# Schematic.net
KiCad netlist of a schematic drawn in EAGLE
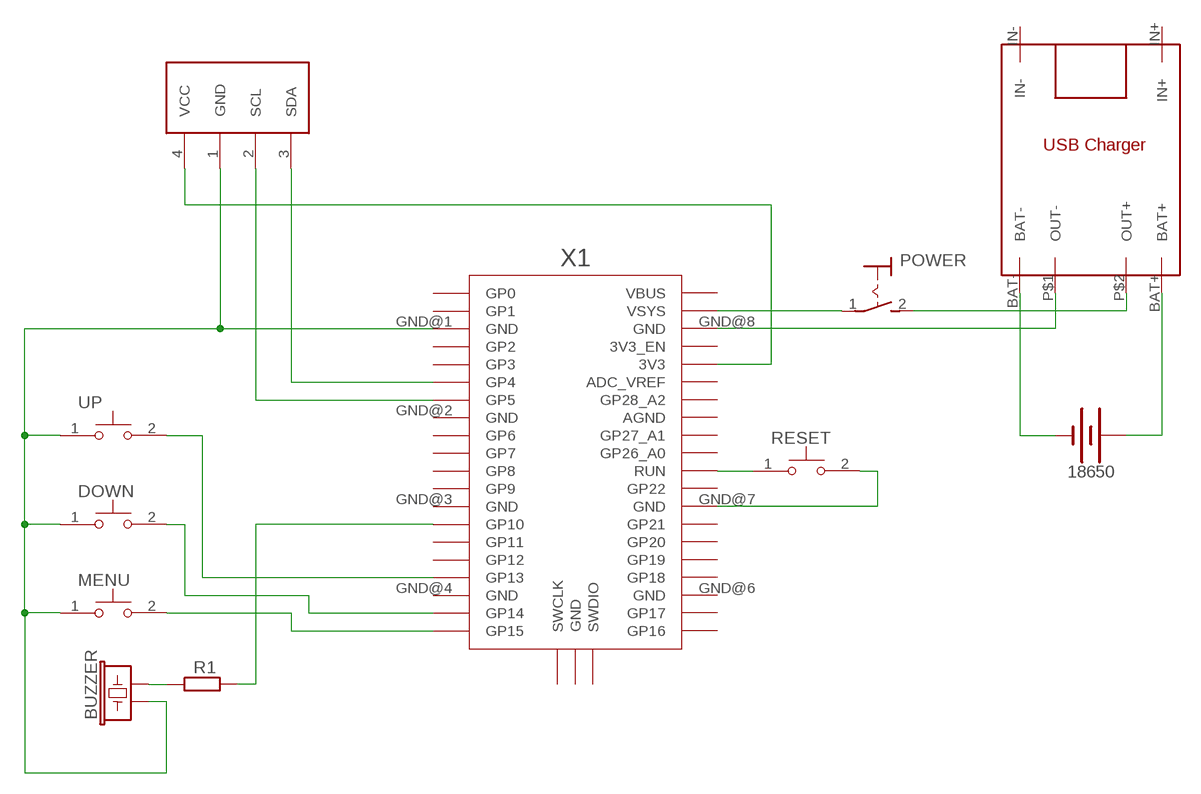
[diagram p0: schematic, sheet 1]

(export (version "E")
  (design (tool "Eeschema 10.0.6"))
  (components
    (comp (ref "18650")
      (value "BATTERY-18650")
      (footprint "eagle-import:BATTERY_18650-HOLDER")
      (libsource (lib "eagle-import") (part "BATTERY-18650"))
    )
    (comp (ref "BUZZER")
      (value "BUZZER-PTH_KIT")
      (footprint "eagle-import:BUZZER-12MM-KIT")
      (libsource (lib "eagle-import") (part "BUZZER-PTH_KIT"))
    )
    (comp (ref "DOWN")
      (value "BUTT-2")
      (footprint "eagle-import:SW_BUTT-2")
      (fields (field (name "MF") "Gravitech"))
      (libsource (lib "eagle-import") (part "BUTT-2"))
    )
    (comp (ref "MENU")
      (value "BUTT-2")
      (footprint "eagle-import:SW_BUTT-2")
      (fields (field (name "MF") "Gravitech"))
      (libsource (lib "eagle-import") (part "BUTT-2"))
    )
    (comp (ref "POWER")
      (value "MS243")
      (footprint "eagle-import:MS243")
      (libsource (lib "eagle-import") (part "MS243"))
    )
    (comp (ref "R1")
      (value "R-EU_0207/10")
      (footprint "eagle-import:0207_10")
      (libsource (lib "eagle-import") (part "R-EU_0207/10"))
    )
    (comp (ref "RESET")
      (value "BUTT-2")
      (footprint "eagle-import:SW_BUTT-2")
      (fields (field (name "MF") "Gravitech"))
      (libsource (lib "eagle-import") (part "BUTT-2"))
    )
    (comp (ref "U$1")
      (value "I2C_OLED")
      (footprint "eagle-import:I2C_OLED_PACKAGE")
      (libsource (lib "eagle-import") (part "I2C_OLED"))
    )
    (comp (ref "U$2")
      (value "TP4056")
      (footprint "eagle-import:TP4056")
      (libsource (lib "eagle-import") (part "TP4056"))
    )
    (comp (ref "UP")
      (value "BUTT-2")
      (footprint "eagle-import:SW_BUTT-2")
      (fields (field (name "MF") "Gravitech"))
      (libsource (lib "eagle-import") (part "BUTT-2"))
    )
    (comp (ref "X1")
      (value "RPI_PICO_IG-TH")
      (footprint "eagle-import:RPI_PICO_TH")
      (libsource (lib "eagle-import") (part "RPI_PICO_IG-TH"))
    )
  )
  (nets
    (net (code "1") (name "Net-(18650-+)") (class "Default")
      (node (ref "18650") (pin "PWR@1") (pinfunction "+_PWR@1") (pintype "power_in"))
      (node (ref "U$2") (pin "BAT+") (pinfunction "BAT+_BAT+") (pintype "bidirectional"))
    )
    (net (code "2") (name "Net-(18650--)") (class "Default")
      (node (ref "18650") (pin "GND@1") (pinfunction "-_GND@1") (pintype "power_in"))
      (node (ref "U$2") (pin "BAT-") (pinfunction "BAT-_BAT-") (pintype "bidirectional"))
    )
    (net (code "3") (name "Net-(BUZZER-1)") (class "Default")
      (node (ref "BUZZER") (pin "+") (pinfunction "1_+") (pintype "passive"))
      (node (ref "DOWN") (pin "1") (pinfunction "1_1") (pintype "passive"))
      (node (ref "MENU") (pin "1") (pinfunction "1_1") (pintype "passive"))
      (node (ref "U$1") (pin "1") (pinfunction "GND_1") (pintype "bidirectional"))
      (node (ref "UP") (pin "1") (pinfunction "1_1") (pintype "passive"))
      (node (ref "X1") (pin "GND@1") (pinfunction "GND_GND@1") (pintype "bidirectional"))
    )
    (net (code "4") (name "Net-(BUZZER-2)") (class "Default")
      (node (ref "BUZZER") (pin "-") (pinfunction "2_-") (pintype "passive"))
      (node (ref "R1") (pin "1") (pinfunction "1_1") (pintype "passive"))
    )
    (net (code "5") (name "Net-(DOWN-Pad2)") (class "Default")
      (node (ref "DOWN") (pin "2") (pinfunction "2_2") (pintype "passive"))
      (node (ref "X1") (pin "GP14") (pinfunction "GP14_GP14") (pintype "bidirectional"))
    )
    (net (code "6") (name "Net-(MENU-Pad2)") (class "Default")
      (node (ref "MENU") (pin "2") (pinfunction "2_2") (pintype "passive"))
      (node (ref "X1") (pin "GP15") (pinfunction "GP15_GP15") (pintype "bidirectional"))
    )
    (net (code "7") (name "Net-(POWER-P)") (class "Default")
      (node (ref "POWER") (pin "1") (pinfunction "P_1") (pintype "passive"))
      (node (ref "X1") (pin "VSYS") (pinfunction "VSYS_VSYS") (pintype "bidirectional"))
    )
    (net (code "8") (name "Net-(POWER-S)") (class "Default")
      (node (ref "POWER") (pin "2") (pinfunction "S_2") (pintype "passive"))
      (node (ref "U$2") (pin "P$2") (pinfunction "OUT+_P$2") (pintype "bidirectional"))
    )
    (net (code "9") (name "Net-(R1-Pad2)") (class "Default")
      (node (ref "R1") (pin "2") (pinfunction "2_2") (pintype "passive"))
      (node (ref "X1") (pin "GP10") (pinfunction "GP10_GP10") (pintype "bidirectional"))
    )
    (net (code "10") (name "Net-(RESET-Pad1)") (class "Default")
      (node (ref "RESET") (pin "1") (pinfunction "1_1") (pintype "passive"))
      (node (ref "X1") (pin "RUN") (pinfunction "RUN_RUN") (pintype "bidirectional"))
    )
    (net (code "11") (name "Net-(RESET-Pad2)") (class "Default")
      (node (ref "RESET") (pin "2") (pinfunction "2_2") (pintype "passive"))
      (node (ref "X1") (pin "GND@7") (pinfunction "GND_GND@7") (pintype "bidirectional"))
    )
    (net (code "12") (name "Net-(U$1-SCL)") (class "Default")
      (node (ref "U$1") (pin "2") (pinfunction "SCL_2") (pintype "bidirectional"))
      (node (ref "X1") (pin "GP5") (pinfunction "GP5_GP5") (pintype "bidirectional"))
    )
    (net (code "13") (name "Net-(U$1-SDA)") (class "Default")
      (node (ref "U$1") (pin "3") (pinfunction "SDA_3") (pintype "bidirectional"))
      (node (ref "X1") (pin "GP4") (pinfunction "GP4_GP4") (pintype "bidirectional"))
    )
    (net (code "14") (name "Net-(U$1-VCC)") (class "Default")
      (node (ref "U$1") (pin "4") (pinfunction "VCC_4") (pintype "bidirectional"))
      (node (ref "X1") (pin "3V3") (pinfunction "3V3_3V3") (pintype "bidirectional"))
    )
    (net (code "15") (name "Net-(U$2-OUT-)") (class "Default")
      (node (ref "U$2") (pin "P$1") (pinfunction "OUT-_P$1") (pintype "bidirectional"))
      (node (ref "X1") (pin "GND@8") (pinfunction "GND_GND@8") (pintype "bidirectional"))
    )
    (net (code "16") (name "Net-(UP-Pad2)") (class "Default")
      (node (ref "UP") (pin "2") (pinfunction "2_2") (pintype "passive"))
      (node (ref "X1") (pin "GP13") (pinfunction "GP13_GP13") (pintype "bidirectional"))
    )
    (net (code "17") (name "unconnected-(U$2-PadIN+)") (class "Default")
      (node (ref "U$2") (pin "IN+") (pinfunction "IN+_IN+") (pintype "bidirectional"))
    )
    (net (code "18") (name "unconnected-(U$2-PadIN-)") (class "Default")
      (node (ref "U$2") (pin "IN-") (pinfunction "IN-_IN-") (pintype "bidirectional"))
    )
    (net (code "19") (name "unconnected-(X1-GND-PadGND@2)") (class "Default")
      (node (ref "X1") (pin "GND@2") (pinfunction "GND_GND@2") (pintype "bidirectional"))
    )
    (net (code "20") (name "unconnected-(X1-GND-PadGND@3)") (class "Default")
      (node (ref "X1") (pin "GND@3") (pinfunction "GND_GND@3") (pintype "bidirectional"))
    )
    (net (code "21") (name "unconnected-(X1-GND-PadGND@4)") (class "Default")
      (node (ref "X1") (pin "GND@4") (pinfunction "GND_GND@4") (pintype "bidirectional"))
    )
    (net (code "22") (name "unconnected-(X1-GND-PadGND@5)") (class "Default")
      (node (ref "X1") (pin "GND@5") (pinfunction "GND_GND@5") (pintype "bidirectional"))
    )
    (net (code "23") (name "unconnected-(X1-GND-PadGND@6)") (class "Default")
      (node (ref "X1") (pin "GND@6") (pinfunction "GND_GND@6") (pintype "bidirectional"))
    )
    (net (code "24") (name "unconnected-(X1-Pad3V3_EN)") (class "Default")
      (node (ref "X1") (pin "3V3_EN") (pinfunction "3V3_EN_3V3_EN") (pintype "bidirectional"))
    )
    (net (code "25") (name "unconnected-(X1-PadADC_VREF)") (class "Default")
      (node (ref "X1") (pin "ADC_VREF") (pinfunction "ADC_VREF_ADC_VREF") (pintype "bidirectional"))
    )
    (net (code "26") (name "unconnected-(X1-PadAGND)") (class "Default")
      (node (ref "X1") (pin "AGND") (pinfunction "AGND_AGND") (pintype "bidirectional"))
    )
    (net (code "27") (name "unconnected-(X1-PadGP0)") (class "Default")
      (node (ref "X1") (pin "GP0") (pinfunction "GP0_GP0") (pintype "bidirectional"))
    )
    (net (code "28") (name "unconnected-(X1-PadGP1)") (class "Default")
      (node (ref "X1") (pin "GP1") (pinfunction "GP1_GP1") (pintype "bidirectional"))
    )
    (net (code "29") (name "unconnected-(X1-PadGP2)") (class "Default")
      (node (ref "X1") (pin "GP2") (pinfunction "GP2_GP2") (pintype "bidirectional"))
    )
    (net (code "30") (name "unconnected-(X1-PadGP3)") (class "Default")
      (node (ref "X1") (pin "GP3") (pinfunction "GP3_GP3") (pintype "bidirectional"))
    )
    (net (code "31") (name "unconnected-(X1-PadGP6)") (class "Default")
      (node (ref "X1") (pin "GP6") (pinfunction "GP6_GP6") (pintype "bidirectional"))
    )
    (net (code "32") (name "unconnected-(X1-PadGP7)") (class "Default")
      (node (ref "X1") (pin "GP7") (pinfunction "GP7_GP7") (pintype "bidirectional"))
    )
    (net (code "33") (name "unconnected-(X1-PadGP8)") (class "Default")
      (node (ref "X1") (pin "GP8") (pinfunction "GP8_GP8") (pintype "bidirectional"))
    )
    (net (code "34") (name "unconnected-(X1-PadGP9)") (class "Default")
      (node (ref "X1") (pin "GP9") (pinfunction "GP9_GP9") (pintype "bidirectional"))
    )
    (net (code "35") (name "unconnected-(X1-PadGP11)") (class "Default")
      (node (ref "X1") (pin "GP11") (pinfunction "GP11_GP11") (pintype "bidirectional"))
    )
    (net (code "36") (name "unconnected-(X1-PadGP12)") (class "Default")
      (node (ref "X1") (pin "GP12") (pinfunction "GP12_GP12") (pintype "bidirectional"))
    )
    (net (code "37") (name "unconnected-(X1-PadGP16)") (class "Default")
      (node (ref "X1") (pin "GP16") (pinfunction "GP16_GP16") (pintype "bidirectional"))
    )
    (net (code "38") (name "unconnected-(X1-PadGP17)") (class "Default")
      (node (ref "X1") (pin "GP17") (pinfunction "GP17_GP17") (pintype "bidirectional"))
    )
    (net (code "39") (name "unconnected-(X1-PadGP18)") (class "Default")
      (node (ref "X1") (pin "GP18") (pinfunction "GP18_GP18") (pintype "bidirectional"))
    )
    (net (code "40") (name "unconnected-(X1-PadGP19)") (class "Default")
      (node (ref "X1") (pin "GP19") (pinfunction "GP19_GP19") (pintype "bidirectional"))
    )
    (net (code "41") (name "unconnected-(X1-PadGP20)") (class "Default")
      (node (ref "X1") (pin "GP20") (pinfunction "GP20_GP20") (pintype "bidirectional"))
    )
    (net (code "42") (name "unconnected-(X1-PadGP21)") (class "Default")
      (node (ref "X1") (pin "GP21") (pinfunction "GP21_GP21") (pintype "bidirectional"))
    )
    (net (code "43") (name "unconnected-(X1-PadGP22)") (class "Default")
      (node (ref "X1") (pin "GP22") (pinfunction "GP22_GP22") (pintype "bidirectional"))
    )
    (net (code "44") (name "unconnected-(X1-PadGP26_A0)") (class "Default")
      (node (ref "X1") (pin "GP26_A0") (pinfunction "GP26_A0_GP26_A0") (pintype "bidirectional"))
    )
    (net (code "45") (name "unconnected-(X1-PadGP27_A1)") (class "Default")
      (node (ref "X1") (pin "GP27_A1") (pinfunction "GP27_A1_GP27_A1") (pintype "bidirectional"))
    )
    (net (code "46") (name "unconnected-(X1-PadGP28_A2)") (class "Default")
      (node (ref "X1") (pin "GP28_A2") (pinfunction "GP28_A2_GP28_A2") (pintype "bidirectional"))
    )
    (net (code "47") (name "unconnected-(X1-PadSWCLK)") (class "Default")
      (node (ref "X1") (pin "SWCLK") (pinfunction "SWCLK_SWCLK") (pintype "bidirectional"))
    )
    (net (code "48") (name "unconnected-(X1-PadSWDIO)") (class "Default")
      (node (ref "X1") (pin "SWDIO") (pinfunction "SWDIO_SWDIO") (pintype "bidirectional"))
    )
    (net (code "49") (name "unconnected-(X1-PadVBUS)") (class "Default")
      (node (ref "X1") (pin "VBUS") (pinfunction "VBUS_VBUS") (pintype "bidirectional"))
    )
  )
)
